# Sheet0-MCU.net
KiCad netlist of a schematic drawn in Altium Designer
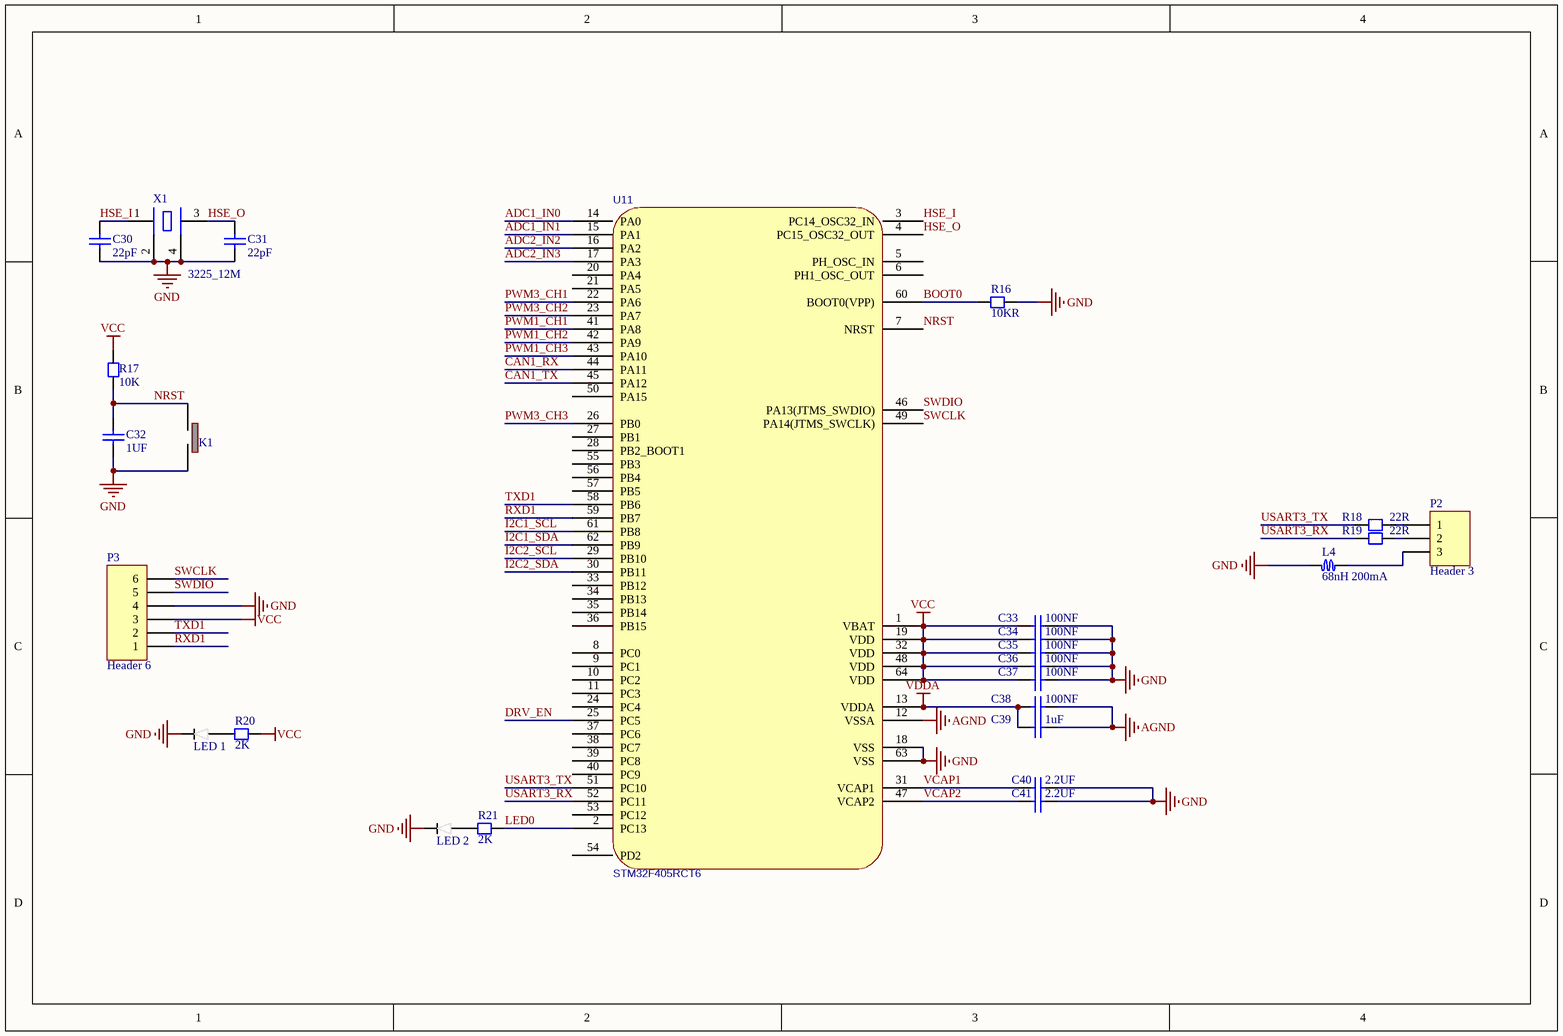
[diagram p0: Sheet0-MCU.SchDoc]

(export (version "E")
  (design (tool "Eeschema 10.0.6"))
  (components
    (comp (ref "C30")
      (value "22pF")
      (footprint "CC1608-0603")
      (description "0603封装的电容")
      (fields (field (name "PUBLISHER") "Altium Limited"))
      (libsource (lib "base") (part "Cap Chip 0603"))
    )
    (comp (ref "C31")
      (value "22pF")
      (footprint "CC1608-0603")
      (description "0603封装的电容")
      (fields (field (name "PUBLISHER") "Altium Limited"))
      (libsource (lib "base") (part "Cap Chip 0603"))
    )
    (comp (ref "C32")
      (value "1UF")
      (footprint "CC1608-0603")
      (description "0603封装的电容")
      (fields (field (name "PUBLISHER") "Altium Limited"))
      (libsource (lib "base") (part "Cap Chip 0603"))
    )
    (comp (ref "C33")
      (value "100NF")
      (footprint "CC1608-0603")
      (description "0603封装的电容")
      (fields (field (name "PUBLISHER") "Altium Limited"))
      (libsource (lib "base") (part "Cap Chip 0603"))
    )
    (comp (ref "C34")
      (value "100NF")
      (footprint "CC1608-0603")
      (description "0603封装的电容")
      (fields (field (name "PUBLISHER") "Altium Limited"))
      (libsource (lib "base") (part "Cap Chip 0603"))
    )
    (comp (ref "C35")
      (value "100NF")
      (footprint "CC1608-0603")
      (description "0603封装的电容")
      (fields (field (name "PUBLISHER") "Altium Limited"))
      (libsource (lib "base") (part "Cap Chip 0603"))
    )
    (comp (ref "C36")
      (value "100NF")
      (footprint "CC1608-0603")
      (description "0603封装的电容")
      (fields (field (name "PUBLISHER") "Altium Limited"))
      (libsource (lib "base") (part "Cap Chip 0603"))
    )
    (comp (ref "C37")
      (value "100NF")
      (footprint "CC1608-0603")
      (description "0603封装的电容")
      (fields (field (name "PUBLISHER") "Altium Limited"))
      (libsource (lib "base") (part "Cap Chip 0603"))
    )
    (comp (ref "C38")
      (value "100NF")
      (footprint "CC1608-0603")
      (description "0603封装的电容")
      (fields (field (name "PUBLISHER") "Altium Limited"))
      (libsource (lib "base") (part "Cap Chip 0603"))
    )
    (comp (ref "C39")
      (value "1uF")
      (footprint "CC1608-0603")
      (description "0603封装的电容")
      (fields (field (name "PUBLISHER") "Altium Limited"))
      (libsource (lib "base") (part "Cap Chip 0603"))
    )
    (comp (ref "C40")
      (value "2.2UF")
      (footprint "CC1608-0603")
      (description "0603封装的电容")
      (fields (field (name "PUBLISHER") "Altium Limited"))
      (libsource (lib "base") (part "Cap Chip 0603"))
    )
    (comp (ref "C41")
      (value "2.2UF")
      (footprint "CC1608-0603")
      (description "0603封装的电容")
      (fields (field (name "PUBLISHER") "Altium Limited"))
      (libsource (lib "base") (part "Cap Chip 0603"))
    )
    (comp (ref "K1")
      (value "KEY 3*4")
      (footprint "KEY 3*4")
      (description "轻触开关按键")
      (libsource (lib "base") (part "KEY 3*4"))
    )
    (comp (ref "L4")
      (value "68nH 200mA")
      (footprint "Inductor-0603")
      (description "贴片电感 0603封装")
      (libsource (lib "base") (part "Inductor-0603"))
    )
    (comp (ref "LED 1") (value "LED 0603") (footprint "LED 0603") (libsource (lib "base") (part "LED 0603")))
    (comp (ref "LED 2") (value "LED 0603") (footprint "LED 0603") (libsource (lib "base") (part "LED 0603")))
    (comp (ref "P2")
      (value "Header 3")
      (footprint "HX2.54-3")
      (description "Header, 3-Pin")
      (fields (field (name "PUBLISHER") "Altium Limited"))
      (libsource (lib "Connectors") (part "Header 3"))
    )
    (comp (ref "P3")
      (value "Header 6")
      (footprint "HDR1X6")
      (description "Header, 6-Pin")
      (fields (field (name "PUBLISHER") "Altium Limited"))
      (libsource (lib "Connectors") (part "Header 6"))
    )
    (comp (ref "R16")
      (value "10KR")
      (footprint "CR1608-0603")
      (description "0603封装电阻")
      (fields (field (name "PUBLISHER") "Altium Limited"))
      (libsource (lib "") (part "Resistor Chip 0603_1"))
    )
    (comp (ref "R17")
      (value "10K")
      (footprint "CR1608-0603")
      (description "0603封装电阻")
      (fields (field (name "PUBLISHER") "Altium Limited"))
      (libsource (lib "") (part "Resistor Chip 0603_2"))
    )
    (comp (ref "R18")
      (value "22R")
      (footprint "CR1608-0603")
      (description "0603封装电阻")
      (fields (field (name "PUBLISHER") "Altium Limited"))
      (libsource (lib "base") (part "Resistor Chip 0603"))
    )
    (comp (ref "R19")
      (value "22R")
      (footprint "CR1608-0603")
      (description "0603封装电阻")
      (fields (field (name "PUBLISHER") "Altium Limited"))
      (libsource (lib "base") (part "Resistor Chip 0603"))
    )
    (comp (ref "R20")
      (value "2K")
      (footprint "CR1608-0603")
      (description "0603封装电阻")
      (fields (field (name "PUBLISHER") "Altium Limited"))
      (libsource (lib "base") (part "Resistor Chip 0603"))
    )
    (comp (ref "R21")
      (value "2K")
      (footprint "CR1608-0603")
      (description "0603封装电阻")
      (fields (field (name "PUBLISHER") "Altium Limited"))
      (libsource (lib "base") (part "Resistor Chip 0603"))
    )
    (comp (ref "U11")
      (value "STM32F405RCT6")
      (footprint "LQFNP64")
      (fields (field (name "CONTRIBUTOR") "czycb"))
      (libsource (lib "singlechip") (part "STM32F405RCT6"))
    )
    (comp (ref "X1")
      (value "3225_12M")
      (footprint "XTAL-3225")
      (description "3225封装的晶振")
      (libsource (lib "base") (part "XTAL 3225"))
    )
  )
  (nets
    (net (code "1") (name "/ADC1_IN0") (class "Default")
      (node (ref "U11") (pin "14") (pinfunction "PA0_14") (pintype "passive"))
    )
    (net (code "2") (name "/ADC1_IN1") (class "Default")
      (node (ref "U11") (pin "15") (pinfunction "PA1_15") (pintype "passive"))
    )
    (net (code "3") (name "/ADC2_IN2") (class "Default")
      (node (ref "U11") (pin "16") (pinfunction "PA2_16") (pintype "passive"))
    )
    (net (code "4") (name "/ADC2_IN3") (class "Default")
      (node (ref "U11") (pin "17") (pinfunction "PA3_17") (pintype "passive"))
    )
    (net (code "5") (name "/BOOT0") (class "Default")
      (node (ref "R16") (pin "2") (pinfunction "2_2") (pintype "passive"))
      (node (ref "U11") (pin "60") (pinfunction "BOOT0(VPP)_60") (pintype "passive"))
    )
    (net (code "6") (name "/CAN1_RX") (class "Default")
      (node (ref "U11") (pin "44") (pinfunction "PA11_44") (pintype "passive"))
    )
    (net (code "7") (name "/CAN1_TX") (class "Default")
      (node (ref "U11") (pin "45") (pinfunction "PA12_45") (pintype "passive"))
    )
    (net (code "8") (name "/DRV_EN") (class "Default")
      (node (ref "U11") (pin "25") (pinfunction "PC5_25") (pintype "passive"))
    )
    (net (code "9") (name "/HSE_I") (class "Default")
      (node (ref "C30") (pin "2") (pinfunction "2_2") (pintype "passive"))
      (node (ref "U11") (pin "3") (pinfunction "PC14_OSC32_IN_3") (pintype "passive"))
      (node (ref "X1") (pin "1") (pinfunction "OSC1_1") (pintype "passive"))
    )
    (net (code "10") (name "/HSE_O") (class "Default")
      (node (ref "C31") (pin "2") (pinfunction "2_2") (pintype "passive"))
      (node (ref "U11") (pin "4") (pinfunction "PC15_OSC32_OUT_4") (pintype "passive"))
      (node (ref "X1") (pin "3") (pinfunction "OSC2_3") (pintype "passive"))
    )
    (net (code "11") (name "/I2C1_SCL") (class "Default")
      (node (ref "U11") (pin "61") (pinfunction "PB8_61") (pintype "passive"))
    )
    (net (code "12") (name "/I2C1_SDA") (class "Default")
      (node (ref "U11") (pin "62") (pinfunction "PB9_62") (pintype "passive"))
    )
    (net (code "13") (name "/I2C2_SCL") (class "Default")
      (node (ref "U11") (pin "29") (pinfunction "PB10_29") (pintype "passive"))
    )
    (net (code "14") (name "/I2C2_SDA") (class "Default")
      (node (ref "U11") (pin "30") (pinfunction "PB11_30") (pintype "passive"))
    )
    (net (code "15") (name "/LED0") (class "Default")
      (node (ref "R21") (pin "2") (pinfunction "2_2") (pintype "passive"))
      (node (ref "U11") (pin "2") (pinfunction "PC13_2") (pintype "passive"))
    )
    (net (code "16") (name "/NRST") (class "Default")
      (node (ref "C32") (pin "2") (pinfunction "2_2") (pintype "passive"))
      (node (ref "K1") (pin "1") (pinfunction "1_1") (pintype "passive"))
      (node (ref "R17") (pin "1") (pinfunction "1_1") (pintype "passive"))
      (node (ref "U11") (pin "7") (pinfunction "NRST_7") (pintype "passive"))
    )
    (net (code "17") (name "/PWM1_CH1") (class "Default")
      (node (ref "U11") (pin "41") (pinfunction "PA8_41") (pintype "passive"))
    )
    (net (code "18") (name "/PWM1_CH2") (class "Default")
      (node (ref "U11") (pin "42") (pinfunction "PA9_42") (pintype "passive"))
    )
    (net (code "19") (name "/PWM1_CH3") (class "Default")
      (node (ref "U11") (pin "43") (pinfunction "PA10_43") (pintype "passive"))
    )
    (net (code "20") (name "/PWM3_CH1") (class "Default")
      (node (ref "U11") (pin "22") (pinfunction "PA6_22") (pintype "passive"))
    )
    (net (code "21") (name "/PWM3_CH2") (class "Default")
      (node (ref "U11") (pin "23") (pinfunction "PA7_23") (pintype "passive"))
    )
    (net (code "22") (name "/PWM3_CH3") (class "Default")
      (node (ref "U11") (pin "26") (pinfunction "PB0_26") (pintype "passive"))
    )
    (net (code "23") (name "/RXD1") (class "Default")
      (node (ref "P3") (pin "1") (pinfunction "1_1") (pintype "passive"))
      (node (ref "U11") (pin "59") (pinfunction "PB7_59") (pintype "passive"))
    )
    (net (code "24") (name "/SWCLK") (class "Default")
      (node (ref "P3") (pin "6") (pinfunction "6_6") (pintype "passive"))
      (node (ref "U11") (pin "49") (pinfunction "PA14(JTMS_SWCLK)_49") (pintype "passive"))
    )
    (net (code "25") (name "/SWDIO") (class "Default")
      (node (ref "P3") (pin "5") (pinfunction "5_5") (pintype "passive"))
      (node (ref "U11") (pin "46") (pinfunction "PA13(JTMS_SWDIO)_46") (pintype "passive"))
    )
    (net (code "26") (name "/TXD1") (class "Default")
      (node (ref "P3") (pin "2") (pinfunction "2_2") (pintype "passive"))
      (node (ref "U11") (pin "58") (pinfunction "PB6_58") (pintype "passive"))
    )
    (net (code "27") (name "/USART3_RX") (class "Default")
      (node (ref "R19") (pin "1") (pinfunction "1_1") (pintype "passive"))
      (node (ref "U11") (pin "52") (pinfunction "PC11_52") (pintype "passive"))
    )
    (net (code "28") (name "/USART3_TX") (class "Default")
      (node (ref "R18") (pin "1") (pinfunction "1_1") (pintype "passive"))
      (node (ref "U11") (pin "51") (pinfunction "PC10_51") (pintype "passive"))
    )
    (net (code "29") (name "/VCAP1") (class "Default")
      (node (ref "C40") (pin "1") (pinfunction "1_1") (pintype "passive"))
      (node (ref "U11") (pin "31") (pinfunction "VCAP1_31") (pintype "passive"))
    )
    (net (code "30") (name "/VCAP2") (class "Default")
      (node (ref "C41") (pin "2") (pinfunction "2_2") (pintype "passive"))
      (node (ref "U11") (pin "47") (pinfunction "VCAP2_47") (pintype "passive"))
    )
    (net (code "31") (name "AGND") (class "Default")
      (node (ref "C38") (pin "1") (pinfunction "1_1") (pintype "passive"))
      (node (ref "C39") (pin "1") (pinfunction "1_1") (pintype "passive"))
      (node (ref "U11") (pin "12") (pinfunction "VSSA_12") (pintype "passive"))
    )
    (net (code "32") (name "GND") (class "Default")
      (node (ref "C30") (pin "1") (pinfunction "1_1") (pintype "passive"))
      (node (ref "C31") (pin "1") (pinfunction "1_1") (pintype "passive"))
      (node (ref "C32") (pin "1") (pinfunction "1_1") (pintype "passive"))
      (node (ref "C33") (pin "1") (pinfunction "1_1") (pintype "passive"))
      (node (ref "C34") (pin "1") (pinfunction "1_1") (pintype "passive"))
      (node (ref "C35") (pin "1") (pinfunction "1_1") (pintype "passive"))
      (node (ref "C36") (pin "1") (pinfunction "1_1") (pintype "passive"))
      (node (ref "C37") (pin "1") (pinfunction "1_1") (pintype "passive"))
      (node (ref "C40") (pin "2") (pinfunction "2_2") (pintype "passive"))
      (node (ref "C41") (pin "1") (pinfunction "1_1") (pintype "passive"))
      (node (ref "K1") (pin "2") (pinfunction "2_2") (pintype "passive"))
      (node (ref "L4") (pin "2") (pinfunction "2_2") (pintype "passive"))
      (node (ref "LED 1") (pin "2") (pinfunction "2_2") (pintype "passive"))
      (node (ref "LED 2") (pin "2") (pinfunction "2_2") (pintype "passive"))
      (node (ref "P3") (pin "4") (pinfunction "4_4") (pintype "passive"))
      (node (ref "R16") (pin "1") (pinfunction "1_1") (pintype "passive"))
      (node (ref "U11") (pin "18") (pinfunction "VSS_18") (pintype "passive"))
      (node (ref "U11") (pin "63") (pinfunction "VSS_63") (pintype "passive"))
      (node (ref "X1") (pin "2") (pinfunction "GND_2") (pintype "passive"))
      (node (ref "X1") (pin "4") (pinfunction "GND_4") (pintype "passive"))
    )
    (net (code "33") (name "Net-(L4-Pad1)") (class "Default")
      (node (ref "L4") (pin "1") (pinfunction "1_1") (pintype "passive"))
      (node (ref "P2") (pin "3") (pinfunction "3_3") (pintype "passive"))
    )
    (net (code "34") (name "Net-(LED 1-Pad1)") (class "Default")
      (node (ref "LED 1") (pin "1") (pinfunction "1_1") (pintype "passive"))
      (node (ref "R20") (pin "1") (pinfunction "1_1") (pintype "passive"))
    )
    (net (code "35") (name "Net-(LED 2-Pad1)") (class "Default")
      (node (ref "LED 2") (pin "1") (pinfunction "1_1") (pintype "passive"))
      (node (ref "R21") (pin "1") (pinfunction "1_1") (pintype "passive"))
    )
    (net (code "36") (name "Net-(P2-Pad1)") (class "Default")
      (node (ref "P2") (pin "1") (pinfunction "1_1") (pintype "passive"))
      (node (ref "R18") (pin "2") (pinfunction "2_2") (pintype "passive"))
    )
    (net (code "37") (name "Net-(P2-Pad2)") (class "Default")
      (node (ref "P2") (pin "2") (pinfunction "2_2") (pintype "passive"))
      (node (ref "R19") (pin "2") (pinfunction "2_2") (pintype "passive"))
    )
    (net (code "38") (name "VCC") (class "Default")
      (node (ref "C33") (pin "2") (pinfunction "2_2") (pintype "passive"))
      (node (ref "C34") (pin "2") (pinfunction "2_2") (pintype "passive"))
      (node (ref "C35") (pin "2") (pinfunction "2_2") (pintype "passive"))
      (node (ref "C36") (pin "2") (pinfunction "2_2") (pintype "passive"))
      (node (ref "C37") (pin "2") (pinfunction "2_2") (pintype "passive"))
      (node (ref "P3") (pin "3") (pinfunction "3_3") (pintype "passive"))
      (node (ref "R17") (pin "2") (pinfunction "2_2") (pintype "passive"))
      (node (ref "R20") (pin "2") (pinfunction "2_2") (pintype "passive"))
      (node (ref "U11") (pin "1") (pinfunction "VBAT_1") (pintype "passive"))
      (node (ref "U11") (pin "19") (pinfunction "VDD_19") (pintype "passive"))
      (node (ref "U11") (pin "32") (pinfunction "VDD_32") (pintype "passive"))
      (node (ref "U11") (pin "48") (pinfunction "VDD_48") (pintype "passive"))
      (node (ref "U11") (pin "64") (pinfunction "VDD_64") (pintype "passive"))
    )
    (net (code "39") (name "VDDA") (class "Default")
      (node (ref "C38") (pin "2") (pinfunction "2_2") (pintype "passive"))
      (node (ref "C39") (pin "2") (pinfunction "2_2") (pintype "passive"))
      (node (ref "U11") (pin "13") (pinfunction "VDDA_13") (pintype "passive"))
    )
    (net (code "40") (name "unconnected-(U11-PA4-Pad20)") (class "Default")
      (node (ref "U11") (pin "20") (pinfunction "PA4_20") (pintype "passive"))
    )
    (net (code "41") (name "unconnected-(U11-PA5-Pad21)") (class "Default")
      (node (ref "U11") (pin "21") (pinfunction "PA5_21") (pintype "passive"))
    )
    (net (code "42") (name "unconnected-(U11-PA15-Pad50)") (class "Default")
      (node (ref "U11") (pin "50") (pinfunction "PA15_50") (pintype "passive"))
    )
    (net (code "43") (name "unconnected-(U11-PB1-Pad27)") (class "Default")
      (node (ref "U11") (pin "27") (pinfunction "PB1_27") (pintype "passive"))
    )
    (net (code "44") (name "unconnected-(U11-PB2_BOOT1-Pad28)") (class "Default")
      (node (ref "U11") (pin "28") (pinfunction "PB2_BOOT1_28") (pintype "passive"))
    )
    (net (code "45") (name "unconnected-(U11-PB3-Pad55)") (class "Default")
      (node (ref "U11") (pin "55") (pinfunction "PB3_55") (pintype "passive"))
    )
    (net (code "46") (name "unconnected-(U11-PB4-Pad56)") (class "Default")
      (node (ref "U11") (pin "56") (pinfunction "PB4_56") (pintype "passive"))
    )
    (net (code "47") (name "unconnected-(U11-PB5-Pad57)") (class "Default")
      (node (ref "U11") (pin "57") (pinfunction "PB5_57") (pintype "passive"))
    )
    (net (code "48") (name "unconnected-(U11-PB12-Pad33)") (class "Default")
      (node (ref "U11") (pin "33") (pinfunction "PB12_33") (pintype "passive"))
    )
    (net (code "49") (name "unconnected-(U11-PB13-Pad34)") (class "Default")
      (node (ref "U11") (pin "34") (pinfunction "PB13_34") (pintype "passive"))
    )
    (net (code "50") (name "unconnected-(U11-PB14-Pad35)") (class "Default")
      (node (ref "U11") (pin "35") (pinfunction "PB14_35") (pintype "passive"))
    )
    (net (code "51") (name "unconnected-(U11-PB15-Pad36)") (class "Default")
      (node (ref "U11") (pin "36") (pinfunction "PB15_36") (pintype "passive"))
    )
    (net (code "52") (name "unconnected-(U11-PC0-Pad8)") (class "Default")
      (node (ref "U11") (pin "8") (pinfunction "PC0_8") (pintype "passive"))
    )
    (net (code "53") (name "unconnected-(U11-PC1-Pad9)") (class "Default")
      (node (ref "U11") (pin "9") (pinfunction "PC1_9") (pintype "passive"))
    )
    (net (code "54") (name "unconnected-(U11-PC2-Pad10)") (class "Default")
      (node (ref "U11") (pin "10") (pinfunction "PC2_10") (pintype "passive"))
    )
    (net (code "55") (name "unconnected-(U11-PC3-Pad11)") (class "Default")
      (node (ref "U11") (pin "11") (pinfunction "PC3_11") (pintype "passive"))
    )
    (net (code "56") (name "unconnected-(U11-PC4-Pad24)") (class "Default")
      (node (ref "U11") (pin "24") (pinfunction "PC4_24") (pintype "passive"))
    )
    (net (code "57") (name "unconnected-(U11-PC6-Pad37)") (class "Default")
      (node (ref "U11") (pin "37") (pinfunction "PC6_37") (pintype "passive"))
    )
    (net (code "58") (name "unconnected-(U11-PC7-Pad38)") (class "Default")
      (node (ref "U11") (pin "38") (pinfunction "PC7_38") (pintype "passive"))
    )
    (net (code "59") (name "unconnected-(U11-PC8-Pad39)") (class "Default")
      (node (ref "U11") (pin "39") (pinfunction "PC8_39") (pintype "passive"))
    )
    (net (code "60") (name "unconnected-(U11-PC9-Pad40)") (class "Default")
      (node (ref "U11") (pin "40") (pinfunction "PC9_40") (pintype "passive"))
    )
    (net (code "61") (name "unconnected-(U11-PC12-Pad53)") (class "Default")
      (node (ref "U11") (pin "53") (pinfunction "PC12_53") (pintype "passive"))
    )
    (net (code "62") (name "unconnected-(U11-PD2-Pad54)") (class "Default")
      (node (ref "U11") (pin "54") (pinfunction "PD2_54") (pintype "passive"))
    )
    (net (code "63") (name "unconnected-(U11-PH1_OSC_OUT-Pad6)") (class "Default")
      (node (ref "U11") (pin "6") (pinfunction "PH1_OSC_OUT_6") (pintype "passive"))
    )
    (net (code "64") (name "unconnected-(U11-PH_OSC_IN-Pad5)") (class "Default")
      (node (ref "U11") (pin "5") (pinfunction "PH_OSC_IN_5") (pintype "passive"))
    )
  )
)
